# Power_Delivery.net
KiCad netlist of a schematic drawn in Altium Designer
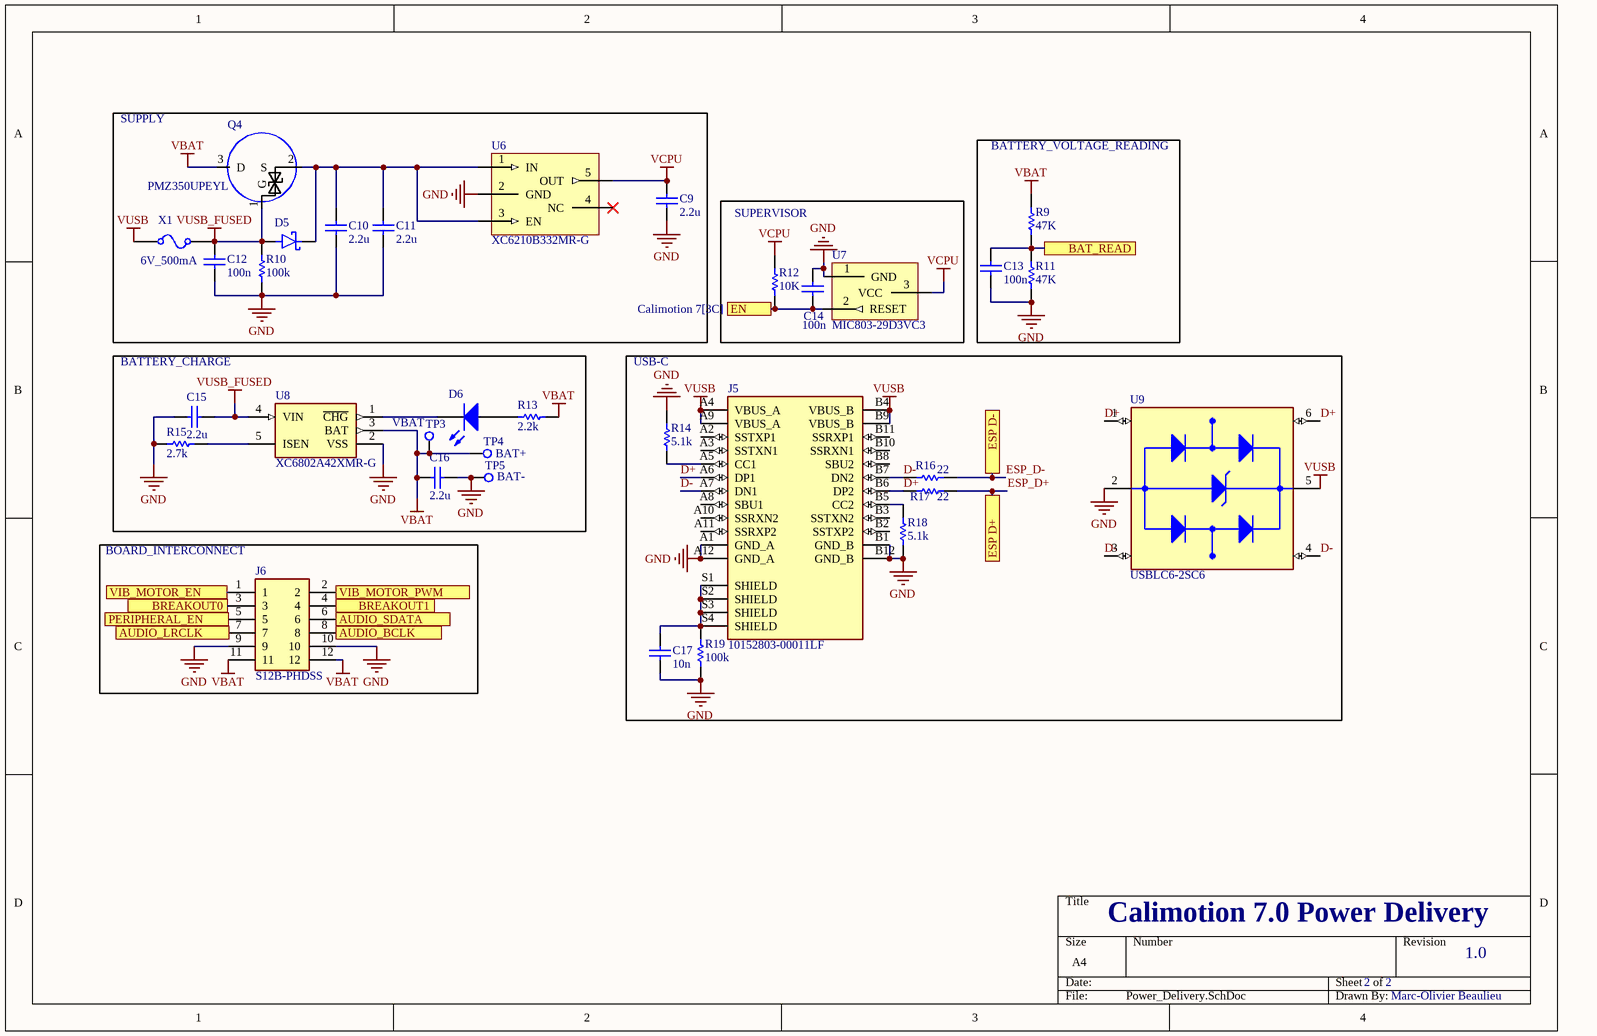
[diagram p0: Power_Delivery.SchDoc]

(export (version "E")
  (design (tool "Eeschema 10.0.6"))
  (components
    (comp (ref "C9")
      (value "2.2u")
      (footprint "CAP 0402_1005")
      (description "Capacitor")
      (libsource (lib "Simulation Generic Components") (part "Capacitor"))
    )
    (comp (ref "C10")
      (value "2.2u")
      (footprint "CAP 0402_1005")
      (description "Capacitor")
      (libsource (lib "Simulation Generic Components") (part "Capacitor"))
    )
    (comp (ref "C11")
      (value "2.2u")
      (footprint "CAP 0402_1005")
      (description "Capacitor")
      (libsource (lib "Simulation Generic Components") (part "Capacitor"))
    )
    (comp (ref "C12")
      (value "100n")
      (footprint "CAP 0402_1005")
      (description "Capacitor")
      (libsource (lib "Simulation Generic Components") (part "Capacitor"))
    )
    (comp (ref "C13")
      (value "100n")
      (footprint "CAP 0402_1005")
      (description "Capacitor")
      (libsource (lib "Simulation Generic Components") (part "Capacitor"))
    )
    (comp (ref "C14")
      (value "100n")
      (footprint "CAP 0402_1005")
      (description "Capacitor")
      (libsource (lib "Simulation Generic Components") (part "Capacitor"))
    )
    (comp (ref "C15")
      (value "2.2u")
      (footprint "CAP 0402_1005")
      (description "Capacitor")
      (libsource (lib "Simulation Generic Components") (part "Capacitor"))
    )
    (comp (ref "C16")
      (value "2.2u")
      (footprint "CAP 0402_1005")
      (description "Capacitor")
      (libsource (lib "Simulation Generic Components") (part "Capacitor"))
    )
    (comp (ref "C17")
      (value "10n")
      (footprint "CAP 0402_1005")
      (description "Capacitor")
      (libsource (lib "Simulation Generic Components") (part "Capacitor"))
    )
    (comp (ref "D5")
      (value "SHOTTKY")
      (footprint "SOD-923")
      (description "Generic Shottky")
      (fields (field (name "MF") "ON Semiconductor") (field (name "MP") "ESD9X5.0ST5G"))
      (libsource (lib "Importred_Components") (part "SHOTTKY"))
    )
    (comp (ref "D6")
      (value "Light-Emitting Diode")
      (footprint "LEDSC160X80X70L45N")
      (libsource (lib "Simulation Generic Components") (part "LED"))
    )
    (comp (ref "J5")
      (value "10152803-00011LF")
      (footprint "AMPHENOL_10152803-00011LF")
      (description "USB 3.2 Type C GEN 2 Receptacle SMT Dual Row 24in")
      (fields (field (name "MF") "Amphenol FCI"))
      (libsource (lib "Importred_Components") (part "10152803-00011LF"))
    )
    (comp (ref "J6")
      (value "S12B-PHDSS")
      (footprint "JST_S12B-PHDSS")
      (description "Connector Header Through Hole, Right Angle 12 position 0.079 _2.00mm_")
      (fields (field (name "MF") "JST Sales") (field (name "MP") "S8B-PHDSS"))
      (libsource (lib "Importred_Components") (part "S12B-PHDSS"))
    )
    (comp (ref "Q4")
      (value "PMZ350UPEYL")
      (footprint "SOT-883")
      (description "P-Channel 20 V 1A (Ta) 360mW (Ta), 3.125W (Tc) Surface Mount SOT-883")
      (libsource (lib "Importred_Components") (part "PMZ350UPEYL"))
    )
    (comp (ref "R9")
      (value "47K")
      (footprint "RES 0402_1005 RF")
      (description "Resistor")
      (libsource (lib "Simulation Generic Components") (part "Resistor"))
    )
    (comp (ref "R10")
      (value "100k")
      (footprint "RES 0402_1005 RF")
      (description "Resistor")
      (libsource (lib "Simulation Generic Components") (part "Resistor"))
    )
    (comp (ref "R11")
      (value "47K")
      (footprint "RES 0402_1005 RF")
      (description "Resistor")
      (libsource (lib "Simulation Generic Components") (part "Resistor"))
    )
    (comp (ref "R12")
      (value "10K")
      (footprint "RES 0402_1005 RF")
      (description "Resistor")
      (libsource (lib "Simulation Generic Components") (part "Resistor"))
    )
    (comp (ref "R13")
      (value "2.2k")
      (footprint "RES 0402_1005 RF")
      (description "Resistor")
      (libsource (lib "Simulation Generic Components") (part "Resistor"))
    )
    (comp (ref "R14")
      (value "5.1k")
      (footprint "RES 0402_1005 RF")
      (description "Resistor")
      (libsource (lib "Simulation Generic Components") (part "Resistor"))
    )
    (comp (ref "R15")
      (value "2.7k")
      (footprint "RES 0402_1005 RF")
      (description "Resistor")
      (libsource (lib "Simulation Generic Components") (part "Resistor"))
    )
    (comp (ref "R16")
      (value "22")
      (footprint "RES 0402_1005 RF")
      (description "Resistor")
      (libsource (lib "Simulation Generic Components") (part "Resistor"))
    )
    (comp (ref "R17")
      (value "22")
      (footprint "RES 0402_1005 RF")
      (description "Resistor")
      (libsource (lib "Simulation Generic Components") (part "Resistor"))
    )
    (comp (ref "R18")
      (value "5.1k")
      (footprint "RES 0402_1005 RF")
      (description "Resistor")
      (libsource (lib "Simulation Generic Components") (part "Resistor"))
    )
    (comp (ref "R19")
      (value "100k")
      (footprint "RES 0402_1005 RF")
      (description "Resistor")
      (libsource (lib "Simulation Generic Components") (part "Resistor"))
    )
    (comp (ref "TP3")
      (value "VBAT")
      (footprint "THT-Test_Point")
      (libsource (lib "Celestial Library") (part "Test Point"))
    )
    (comp (ref "TP4")
      (value "BAT+")
      (footprint "THT-Test_Point")
      (libsource (lib "Celestial Library") (part "Test Point"))
    )
    (comp (ref "TP5")
      (value "BAT-")
      (footprint "THT-Test_Point")
      (libsource (lib "Celestial Library") (part "Test Point"))
    )
    (comp (ref "U6")
      (value "XC6210B332MR-G")
      (footprint "SOT-25")
      (description "Linear Voltage Regulator IC Positive Fixed 1 Output 700mA SOT-25")
      (libsource (lib "Importred_Components") (part "XC6210B332MR-G"))
    )
    (comp (ref "U7")
      (value "MIC803-29D3VC3")
      (footprint "MIC803-29D3VC3")
      (description "Supervisor Open Drain or Open Collector 1 Channel SC-70-3 Voltage - Threshold 2.93V")
      (libsource (lib "Importred_Components") (part "MIC803-29D3VC3"))
    )
    (comp (ref "U8")
      (value "XC6802A42XMR-G")
      (footprint "SOT-25")
      (description "Charger IC Lithium Ion/Polymer SOT-25")
      (fields (field (name "MF") "Torex"))
      (libsource (lib "Importred_Components") (part "XC6802A42XMR-G"))
    )
    (comp (ref "U9")
      (value "USBLC6-2SC6")
      (footprint "SOT95P280X145-6N")
      (description "17V Clamp 5A (8/20Âµs) Ipp Tvs Diode Surface Mount SOT-23-6")
      (fields (field (name "MF") "STMicroelectronics"))
      (libsource (lib "Importred_Components") (part "USBLC6-2SC6"))
    )
    (comp (ref "X1")
      (value "Fuse")
      (footprint "RES 0402_1005 RF")
      (fields (field (name "CURRENT") "6V_500mA"))
      (libsource (lib "Simulation Generic Components") (part "Fuse"))
    )
  )
  (nets
    (net (code "1") (name "/AUDIO_BCLK") (class "Default")
      (node (ref "J6") (pin "8") (pinfunction "8_8") (pintype "passive"))
    )
    (net (code "2") (name "/AUDIO_LRCLK") (class "Default")
      (node (ref "J6") (pin "7") (pinfunction "7_7") (pintype "passive"))
    )
    (net (code "3") (name "/AUDIO_SDATA") (class "Default")
      (node (ref "J6") (pin "6") (pinfunction "6_6") (pintype "passive"))
    )
    (net (code "4") (name "/BAT_READ") (class "Default")
      (node (ref "C13") (pin "1") (pinfunction "1_1") (pintype "passive"))
      (node (ref "R11") (pin "1") (pinfunction "1_1") (pintype "passive"))
      (node (ref "R9") (pin "2") (pinfunction "2_2") (pintype "passive"))
    )
    (net (code "5") (name "/BREAKOUT0") (class "Default")
      (node (ref "J6") (pin "3") (pinfunction "3_3") (pintype "passive"))
    )
    (net (code "6") (name "/BREAKOUT1") (class "Default")
      (node (ref "J6") (pin "4") (pinfunction "4_4") (pintype "passive"))
    )
    (net (code "7") (name "/D+") (class "Default")
      (node (ref "J5") (pin "A6") (pinfunction "DP1_A6") (pintype "bidirectional"))
      (node (ref "J5") (pin "B6") (pinfunction "DP2_B6") (pintype "bidirectional"))
      (node (ref "R17") (pin "1") (pinfunction "1_1") (pintype "passive"))
      (node (ref "U9") (pin "1") (pinfunction "I/O1_IN_1") (pintype "bidirectional"))
      (node (ref "U9") (pin "6") (pinfunction "I/O1_OUT_6") (pintype "bidirectional"))
    )
    (net (code "8") (name "/D-") (class "Default")
      (node (ref "J5") (pin "A7") (pinfunction "DN1_A7") (pintype "bidirectional"))
      (node (ref "J5") (pin "B7") (pinfunction "DN2_B7") (pintype "bidirectional"))
      (node (ref "R16") (pin "1") (pinfunction "1_1") (pintype "passive"))
      (node (ref "U9") (pin "3") (pinfunction "I/O2_IN_3") (pintype "bidirectional"))
      (node (ref "U9") (pin "4") (pinfunction "I/O2_OUT_4") (pintype "bidirectional"))
    )
    (net (code "9") (name "/EN") (class "Default")
      (node (ref "C14") (pin "2") (pinfunction "2_2") (pintype "passive"))
      (node (ref "R12") (pin "1") (pinfunction "1_1") (pintype "passive"))
      (node (ref "U7") (pin "2") (pinfunction "RESET_2") (pintype "output"))
    )
    (net (code "10") (name "/ESP_D+") (class "Default")
      (node (ref "R17") (pin "2") (pinfunction "2_2") (pintype "passive"))
    )
    (net (code "11") (name "/ESP_D-") (class "Default")
      (node (ref "R16") (pin "2") (pinfunction "2_2") (pintype "passive"))
    )
    (net (code "12") (name "/PERIPHERAL_EN") (class "Default")
      (node (ref "J6") (pin "5") (pinfunction "5_5") (pintype "passive"))
    )
    (net (code "13") (name "/VIB_MOTOR_EN") (class "Default")
      (node (ref "J6") (pin "1") (pinfunction "1_1") (pintype "passive"))
    )
    (net (code "14") (name "/VIB_MOTOR_PWM") (class "Default")
      (node (ref "J6") (pin "2") (pinfunction "2_2") (pintype "passive"))
    )
    (net (code "15") (name "GND") (class "Default")
      (node (ref "C10") (pin "2") (pinfunction "2_2") (pintype "passive"))
      (node (ref "C11") (pin "2") (pinfunction "2_2") (pintype "passive"))
      (node (ref "C12") (pin "1") (pinfunction "1_1") (pintype "passive"))
      (node (ref "C13") (pin "2") (pinfunction "2_2") (pintype "passive"))
      (node (ref "C14") (pin "1") (pinfunction "1_1") (pintype "passive"))
      (node (ref "C15") (pin "2") (pinfunction "2_2") (pintype "passive"))
      (node (ref "C16") (pin "1") (pinfunction "1_1") (pintype "passive"))
      (node (ref "C17") (pin "2") (pinfunction "2_2") (pintype "passive"))
      (node (ref "C9") (pin "1") (pinfunction "1_1") (pintype "passive"))
      (node (ref "J5") (pin "A1") (pinfunction "GND_A_A1") (pintype "power_in"))
      (node (ref "J5") (pin "A12") (pinfunction "GND_A_A12") (pintype "power_in"))
      (node (ref "J5") (pin "B1") (pinfunction "GND_B_B1") (pintype "power_in"))
      (node (ref "J5") (pin "B12") (pinfunction "GND_B_B12") (pintype "power_in"))
      (node (ref "J6") (pin "10") (pinfunction "10_10") (pintype "passive"))
      (node (ref "J6") (pin "9") (pinfunction "9_9") (pintype "passive"))
      (node (ref "R10") (pin "2") (pinfunction "2_2") (pintype "passive"))
      (node (ref "R11") (pin "2") (pinfunction "2_2") (pintype "passive"))
      (node (ref "R14") (pin "2") (pinfunction "2_2") (pintype "passive"))
      (node (ref "R15") (pin "2") (pinfunction "2_2") (pintype "passive"))
      (node (ref "R18") (pin "1") (pinfunction "1_1") (pintype "passive"))
      (node (ref "R19") (pin "2") (pinfunction "2_2") (pintype "passive"))
      (node (ref "TP5") (pin "1") (pinfunction "TP_1") (pintype "passive"))
      (node (ref "U6") (pin "2") (pinfunction "GND_2") (pintype "power_in"))
      (node (ref "U7") (pin "1") (pinfunction "GND_1") (pintype "power_in"))
      (node (ref "U8") (pin "2") (pinfunction "VSS_2") (pintype "power_in"))
      (node (ref "U9") (pin "2") (pinfunction "GND_2") (pintype "power_in"))
    )
    (net (code "16") (name "Net-(C17-Pad1)") (class "Default")
      (node (ref "C17") (pin "1") (pinfunction "1_1") (pintype "passive"))
      (node (ref "J5") (pin "S1") (pinfunction "SHIELD_S1") (pintype "passive"))
      (node (ref "J5") (pin "S2") (pinfunction "SHIELD_S2") (pintype "passive"))
      (node (ref "J5") (pin "S3") (pinfunction "SHIELD_S3") (pintype "passive"))
      (node (ref "J5") (pin "S4") (pinfunction "SHIELD_S4") (pintype "passive"))
      (node (ref "R19") (pin "1") (pinfunction "1_1") (pintype "passive"))
    )
    (net (code "17") (name "Net-(D5-K)") (class "Default")
      (node (ref "C10") (pin "1") (pinfunction "1_1") (pintype "passive"))
      (node (ref "C11") (pin "1") (pinfunction "1_1") (pintype "passive"))
      (node (ref "D5") (pin "C") (pinfunction "K_C") (pintype "passive"))
      (node (ref "Q4") (pin "2") (pinfunction "S_2") (pintype "passive"))
      (node (ref "U6") (pin "1") (pinfunction "IN_1") (pintype "input"))
      (node (ref "U6") (pin "3") (pinfunction "EN_3") (pintype "input"))
    )
    (net (code "18") (name "Net-(D6-A)") (class "Default")
      (node (ref "D6") (pin "1") (pinfunction "A_1") (pintype "passive"))
      (node (ref "R13") (pin "2") (pinfunction "2_2") (pintype "passive"))
    )
    (net (code "19") (name "Net-(D6-K)") (class "Default")
      (node (ref "D6") (pin "2") (pinfunction "K_2") (pintype "passive"))
      (node (ref "U8") (pin "1") (pinfunction "~{CHG}_1") (pintype "output"))
    )
    (net (code "20") (name "Net-(J5-CC1)") (class "Default")
      (node (ref "J5") (pin "A5") (pinfunction "CC1_A5") (pintype "bidirectional"))
      (node (ref "R14") (pin "1") (pinfunction "1_1") (pintype "passive"))
    )
    (net (code "21") (name "Net-(J5-CC2)") (class "Default")
      (node (ref "J5") (pin "B5") (pinfunction "CC2_B5") (pintype "bidirectional"))
      (node (ref "R18") (pin "2") (pinfunction "2_2") (pintype "passive"))
    )
    (net (code "22") (name "Net-(U8-ISEN)") (class "Default")
      (node (ref "R15") (pin "1") (pinfunction "1_1") (pintype "passive"))
      (node (ref "U8") (pin "5") (pinfunction "ISEN_5") (pintype "passive"))
    )
    (net (code "23") (name "VBAT") (class "Default")
      (node (ref "C16") (pin "2") (pinfunction "2_2") (pintype "passive"))
      (node (ref "J6") (pin "11") (pinfunction "11_11") (pintype "passive"))
      (node (ref "J6") (pin "12") (pinfunction "12_12") (pintype "passive"))
      (node (ref "Q4") (pin "3") (pinfunction "D_3") (pintype "passive"))
      (node (ref "R13") (pin "1") (pinfunction "1_1") (pintype "passive"))
      (node (ref "R9") (pin "1") (pinfunction "1_1") (pintype "passive"))
      (node (ref "TP3") (pin "1") (pinfunction "TP_1") (pintype "passive"))
      (node (ref "TP4") (pin "1") (pinfunction "TP_1") (pintype "passive"))
      (node (ref "U8") (pin "3") (pinfunction "BAT_3") (pintype "output"))
    )
    (net (code "24") (name "VCPU") (class "Default")
      (node (ref "C9") (pin "2") (pinfunction "2_2") (pintype "passive"))
      (node (ref "R12") (pin "2") (pinfunction "2_2") (pintype "passive"))
      (node (ref "U6") (pin "5") (pinfunction "OUT_5") (pintype "output"))
      (node (ref "U7") (pin "3") (pinfunction "VCC_3") (pintype "power_in"))
    )
    (net (code "25") (name "VUSB") (class "Default")
      (node (ref "J5") (pin "A4") (pinfunction "VBUS_A_A4") (pintype "power_in"))
      (node (ref "J5") (pin "A9") (pinfunction "VBUS_A_A9") (pintype "power_in"))
      (node (ref "J5") (pin "B4") (pinfunction "VBUS_B_B4") (pintype "power_in"))
      (node (ref "J5") (pin "B9") (pinfunction "VBUS_B_B9") (pintype "power_in"))
      (node (ref "U9") (pin "5") (pinfunction "VBUS_5") (pintype "power_in"))
      (node (ref "X1") (pin "1") (pinfunction "1_1") (pintype "passive"))
    )
    (net (code "26") (name "VUSB_FUSED") (class "Default")
      (node (ref "C12") (pin "2") (pinfunction "2_2") (pintype "passive"))
      (node (ref "C15") (pin "1") (pinfunction "1_1") (pintype "passive"))
      (node (ref "D5") (pin "A") (pinfunction "A_A") (pintype "passive"))
      (node (ref "Q4") (pin "1") (pinfunction "G_1") (pintype "passive"))
      (node (ref "R10") (pin "1") (pinfunction "1_1") (pintype "passive"))
      (node (ref "U8") (pin "4") (pinfunction "VIN_4") (pintype "input"))
      (node (ref "X1") (pin "2") (pinfunction "2_2") (pintype "passive"))
    )
    (net (code "27") (name "unconnected-(J5-SBU1-PadA8)") (class "Default")
      (node (ref "J5") (pin "A8") (pinfunction "SBU1_A8") (pintype "bidirectional"))
    )
    (net (code "28") (name "unconnected-(J5-SBU2-PadB8)") (class "Default")
      (node (ref "J5") (pin "B8") (pinfunction "SBU2_B8") (pintype "bidirectional"))
    )
    (net (code "29") (name "unconnected-(J5-SSRXN1-PadB10)") (class "Default")
      (node (ref "J5") (pin "B10") (pinfunction "SSRXN1_B10") (pintype "bidirectional"))
    )
    (net (code "30") (name "unconnected-(J5-SSRXN2-PadA10)") (class "Default")
      (node (ref "J5") (pin "A10") (pinfunction "SSRXN2_A10") (pintype "bidirectional"))
    )
    (net (code "31") (name "unconnected-(J5-SSRXP1-PadB11)") (class "Default")
      (node (ref "J5") (pin "B11") (pinfunction "SSRXP1_B11") (pintype "bidirectional"))
    )
    (net (code "32") (name "unconnected-(J5-SSRXP2-PadA11)") (class "Default")
      (node (ref "J5") (pin "A11") (pinfunction "SSRXP2_A11") (pintype "bidirectional"))
    )
    (net (code "33") (name "unconnected-(J5-SSTXN1-PadA3)") (class "Default")
      (node (ref "J5") (pin "A3") (pinfunction "SSTXN1_A3") (pintype "bidirectional"))
    )
    (net (code "34") (name "unconnected-(J5-SSTXN2-PadB3)") (class "Default")
      (node (ref "J5") (pin "B3") (pinfunction "SSTXN2_B3") (pintype "bidirectional"))
    )
    (net (code "35") (name "unconnected-(J5-SSTXP1-PadA2)") (class "Default")
      (node (ref "J5") (pin "A2") (pinfunction "SSTXP1_A2") (pintype "bidirectional"))
    )
    (net (code "36") (name "unconnected-(J5-SSTXP2-PadB2)") (class "Default")
      (node (ref "J5") (pin "B2") (pinfunction "SSTXP2_B2") (pintype "bidirectional"))
    )
    (net (code "37") (name "unconnected-(U6-NC-Pad4)") (class "Default")
      (node (ref "U6") (pin "4") (pinfunction "NC_4") (pintype "passive+no_connect"))
    )
  )
)
